# expansion_module_triple_I2C.net
KiCad netlist of a schematic drawn in EAGLE
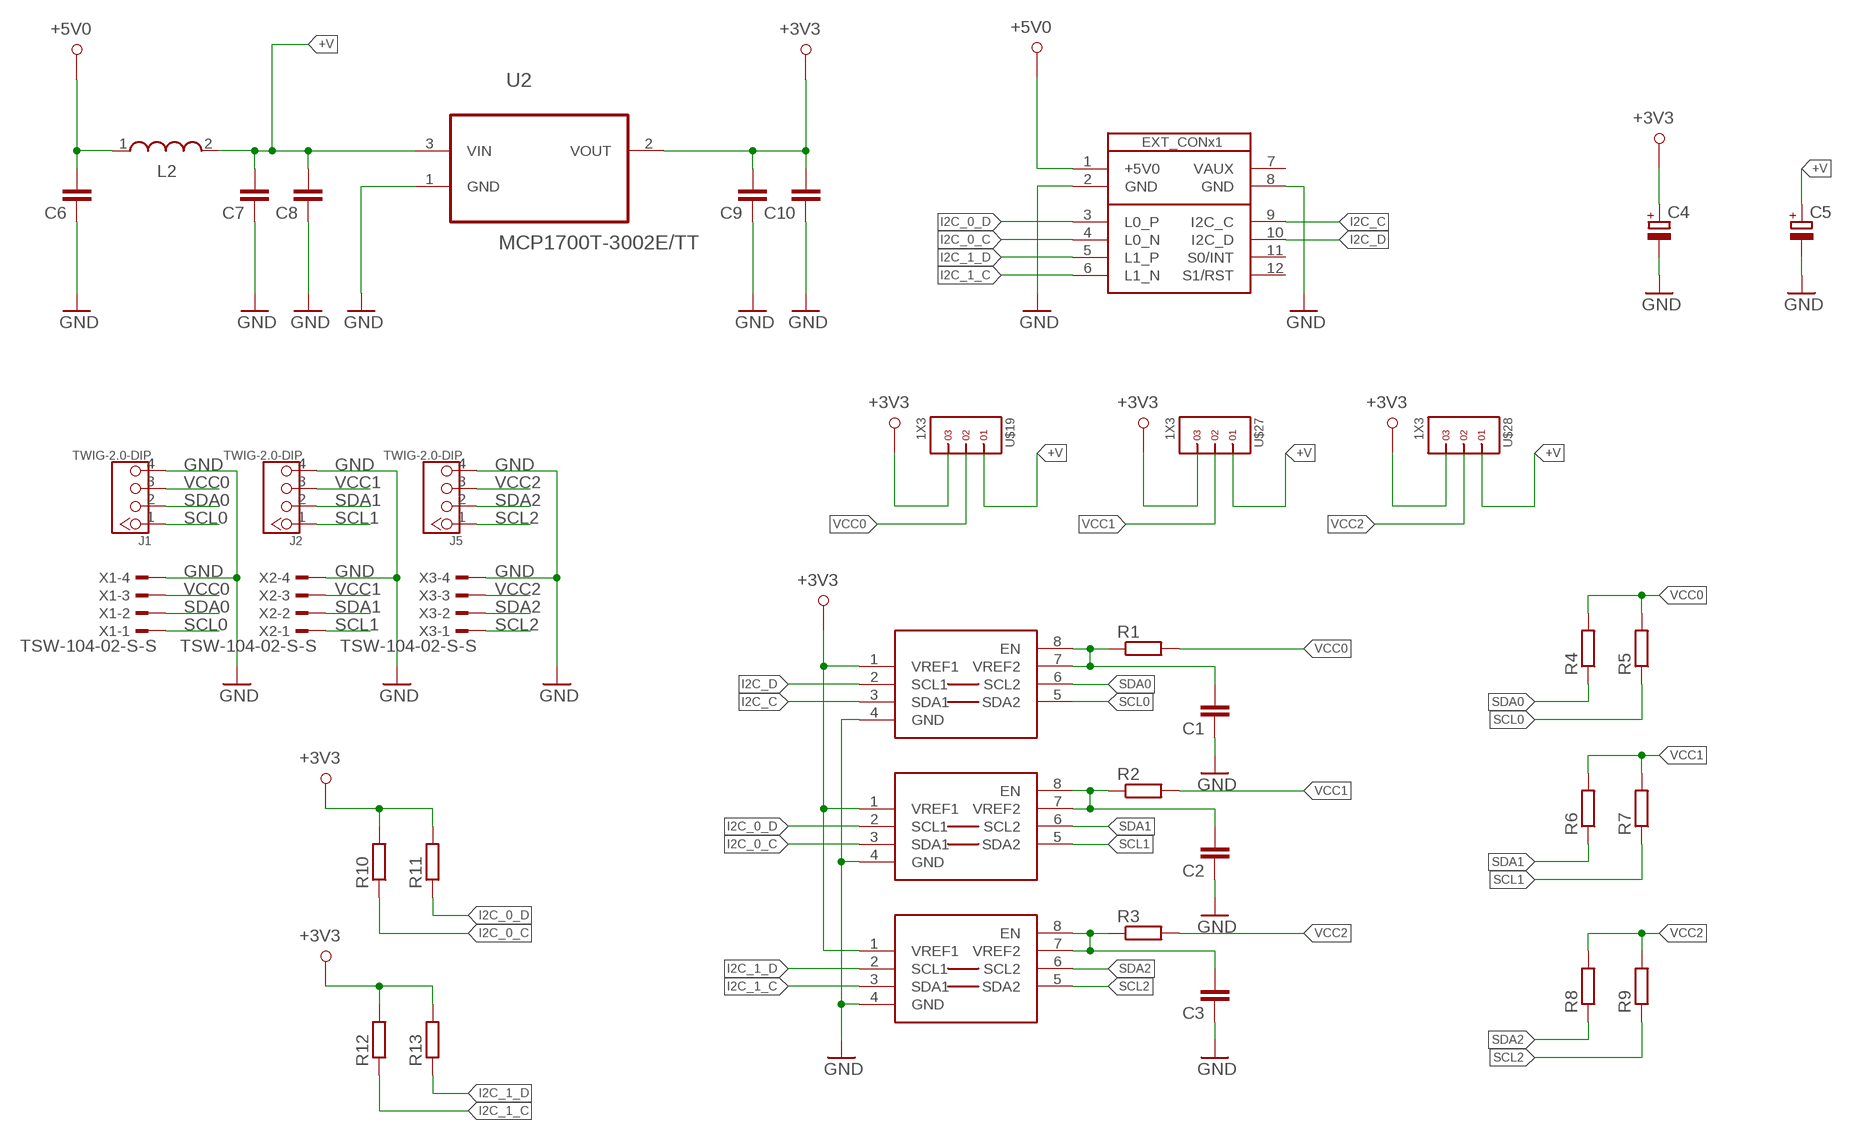
[diagram p0: schematic, sheet 1]

(export (version "E")
  (design (tool "Eeschema 10.0.6"))
  (components
    (comp (ref "C1")
      (value "C-EUC0603")
      (footprint "eagle-import:C0603")
      (libsource (lib "eagle-import") (part "C-EUC0603"))
    )
    (comp (ref "C2")
      (value "C-EUC0603")
      (footprint "eagle-import:C0603")
      (libsource (lib "eagle-import") (part "C-EUC0603"))
    )
    (comp (ref "C3")
      (value "C-EUC0603")
      (footprint "eagle-import:C0603")
      (libsource (lib "eagle-import") (part "C-EUC0603"))
    )
    (comp (ref "C4")
      (value "CPOL-EUSMCB")
      (footprint "eagle-import:SMC_B")
      (libsource (lib "eagle-import") (part "CPOL-EUSMCB"))
    )
    (comp (ref "C5")
      (value "CPOL-EUSMCB")
      (footprint "eagle-import:SMC_B")
      (libsource (lib "eagle-import") (part "CPOL-EUSMCB"))
    )
    (comp (ref "C6")
      (value "C-EUC0603")
      (footprint "eagle-import:C0603")
      (libsource (lib "eagle-import") (part "C-EUC0603"))
    )
    (comp (ref "C7")
      (value "C-EUC0603")
      (footprint "eagle-import:C0603")
      (libsource (lib "eagle-import") (part "C-EUC0603"))
    )
    (comp (ref "C8")
      (value "C-EUC0603")
      (footprint "eagle-import:C0603")
      (libsource (lib "eagle-import") (part "C-EUC0603"))
    )
    (comp (ref "C9")
      (value "C-EUC0603")
      (footprint "eagle-import:C0603")
      (libsource (lib "eagle-import") (part "C-EUC0603"))
    )
    (comp (ref "C10")
      (value "C-EUC0603")
      (footprint "eagle-import:C0603")
      (libsource (lib "eagle-import") (part "C-EUC0603"))
    )
    (comp (ref "J1")
      (value "TWIG-2.0-DIP")
      (footprint "eagle-import:2.0_1X4")
      (libsource (lib "eagle-import") (part "TWIG-2.0-DIP"))
    )
    (comp (ref "J2")
      (value "TWIG-2.0-DIP")
      (footprint "eagle-import:2.0_1X4")
      (libsource (lib "eagle-import") (part "TWIG-2.0-DIP"))
    )
    (comp (ref "J5")
      (value "TWIG-2.0-DIP")
      (footprint "eagle-import:2.0_1X4")
      (libsource (lib "eagle-import") (part "TWIG-2.0-DIP"))
    )
    (comp (ref "L2")
      (value "WE-LQ_1210")
      (footprint "eagle-import:WE-LQ_M")
      (libsource (lib "eagle-import") (part "WE-LQ_1210"))
    )
    (comp (ref "R1")
      (value "R-EU_R0603")
      (footprint "eagle-import:R0603")
      (libsource (lib "eagle-import") (part "R-EU_R0603"))
    )
    (comp (ref "R2")
      (value "R-EU_R0603")
      (footprint "eagle-import:R0603")
      (libsource (lib "eagle-import") (part "R-EU_R0603"))
    )
    (comp (ref "R3")
      (value "R-EU_R0603")
      (footprint "eagle-import:R0603")
      (libsource (lib "eagle-import") (part "R-EU_R0603"))
    )
    (comp (ref "R4")
      (value "R-EU_R0603")
      (footprint "eagle-import:R0603")
      (libsource (lib "eagle-import") (part "R-EU_R0603"))
    )
    (comp (ref "R5")
      (value "R-EU_R0603")
      (footprint "eagle-import:R0603")
      (libsource (lib "eagle-import") (part "R-EU_R0603"))
    )
    (comp (ref "R6")
      (value "R-EU_R0603")
      (footprint "eagle-import:R0603")
      (libsource (lib "eagle-import") (part "R-EU_R0603"))
    )
    (comp (ref "R7")
      (value "R-EU_R0603")
      (footprint "eagle-import:R0603")
      (libsource (lib "eagle-import") (part "R-EU_R0603"))
    )
    (comp (ref "R8")
      (value "R-EU_R0603")
      (footprint "eagle-import:R0603")
      (libsource (lib "eagle-import") (part "R-EU_R0603"))
    )
    (comp (ref "R9")
      (value "R-EU_R0603")
      (footprint "eagle-import:R0603")
      (libsource (lib "eagle-import") (part "R-EU_R0603"))
    )
    (comp (ref "R10")
      (value "R-EU_R0603")
      (footprint "eagle-import:R0603")
      (libsource (lib "eagle-import") (part "R-EU_R0603"))
    )
    (comp (ref "R11")
      (value "R-EU_R0603")
      (footprint "eagle-import:R0603")
      (libsource (lib "eagle-import") (part "R-EU_R0603"))
    )
    (comp (ref "R12")
      (value "R-EU_R0603")
      (footprint "eagle-import:R0603")
      (libsource (lib "eagle-import") (part "R-EU_R0603"))
    )
    (comp (ref "R13")
      (value "R-EU_R0603")
      (footprint "eagle-import:R0603")
      (libsource (lib "eagle-import") (part "R-EU_R0603"))
    )
    (comp (ref "U$2")
      (value "SB_EXT_CON_X1")
      (footprint "eagle-import:SB_EXT_CON_X1_FULL")
      (libsource (lib "eagle-import") (part "SB_EXT_CON_X1"))
    )
    (comp (ref "U$16")
      (value "PCA9306")
      (footprint "eagle-import:PSOP-8")
      (libsource (lib "eagle-import") (part "PCA9306"))
    )
    (comp (ref "U$19")
      (value "1X3")
      (footprint "eagle-import:1X3")
      (libsource (lib "eagle-import") (part "1X3"))
    )
    (comp (ref "U$20")
      (value "PCA9306")
      (footprint "eagle-import:PSOP-8")
      (libsource (lib "eagle-import") (part "PCA9306"))
    )
    (comp (ref "U$27")
      (value "1X3")
      (footprint "eagle-import:1X3")
      (libsource (lib "eagle-import") (part "1X3"))
    )
    (comp (ref "U$28")
      (value "1X3")
      (footprint "eagle-import:1X3")
      (libsource (lib "eagle-import") (part "1X3"))
    )
    (comp (ref "U$31")
      (value "PCA9306")
      (footprint "eagle-import:PSOP-8")
      (libsource (lib "eagle-import") (part "PCA9306"))
    )
    (comp (ref "U2")
      (value "MCP1700T-3002E/TT")
      (footprint "eagle-import:SOT95P237X112-3N")
      (libsource (lib "eagle-import") (part "MCP1700T-3002E/TT"))
    )
    (comp (ref "X1")
      (value "TSW-104-02-S-S")
      (footprint "eagle-import:TSW-104-02-S-S")
      (libsource (lib "eagle-import") (part "TSW-104-02-S-S"))
    )
    (comp (ref "X2")
      (value "TSW-104-02-S-S")
      (footprint "eagle-import:TSW-104-02-S-S")
      (libsource (lib "eagle-import") (part "TSW-104-02-S-S"))
    )
    (comp (ref "X3")
      (value "TSW-104-02-S-S")
      (footprint "eagle-import:TSW-104-02-S-S")
      (libsource (lib "eagle-import") (part "TSW-104-02-S-S"))
    )
  )
  (nets
    (net (code "1") (name "+3V3") (class "Default")
      (node (ref "C10") (pin "2") (pinfunction "2_2") (pintype "passive"))
      (node (ref "C4") (pin "+") (pinfunction "+_+") (pintype "passive"))
      (node (ref "C9") (pin "2") (pinfunction "2_2") (pintype "passive"))
      (node (ref "R10") (pin "2") (pinfunction "2_2") (pintype "passive"))
      (node (ref "R11") (pin "2") (pinfunction "2_2") (pintype "passive"))
      (node (ref "R12") (pin "2") (pinfunction "2_2") (pintype "passive"))
      (node (ref "R13") (pin "2") (pinfunction "2_2") (pintype "passive"))
      (node (ref "U$16") (pin "1") (pinfunction "VREF1_1") (pintype "bidirectional"))
      (node (ref "U$19") (pin "3") (pinfunction "3_3") (pintype "bidirectional"))
      (node (ref "U$20") (pin "1") (pinfunction "VREF1_1") (pintype "bidirectional"))
      (node (ref "U$27") (pin "3") (pinfunction "3_3") (pintype "bidirectional"))
      (node (ref "U$28") (pin "3") (pinfunction "3_3") (pintype "bidirectional"))
      (node (ref "U$31") (pin "1") (pinfunction "VREF1_1") (pintype "bidirectional"))
      (node (ref "U2") (pin "2") (pinfunction "VOUT_2") (pintype "output"))
    )
    (net (code "2") (name "+5V0") (class "Default")
      (node (ref "C6") (pin "2") (pinfunction "2_2") (pintype "passive"))
      (node (ref "L2") (pin "1") (pinfunction "1_1") (pintype "passive"))
      (node (ref "U$2") (pin "1") (pinfunction "+5V0_1") (pintype "bidirectional"))
    )
    (net (code "3") (name "+V") (class "Default")
      (node (ref "C5") (pin "+") (pinfunction "+_+") (pintype "passive"))
      (node (ref "C7") (pin "2") (pinfunction "2_2") (pintype "passive"))
      (node (ref "C8") (pin "2") (pinfunction "2_2") (pintype "passive"))
      (node (ref "L2") (pin "2") (pinfunction "2_2") (pintype "passive"))
      (node (ref "U$19") (pin "1") (pinfunction "1_1") (pintype "bidirectional"))
      (node (ref "U$27") (pin "1") (pinfunction "1_1") (pintype "bidirectional"))
      (node (ref "U$28") (pin "1") (pinfunction "1_1") (pintype "bidirectional"))
      (node (ref "U2") (pin "3") (pinfunction "VIN_3") (pintype "input"))
    )
    (net (code "4") (name "GND") (class "Default")
      (node (ref "C1") (pin "1") (pinfunction "1_1") (pintype "passive"))
      (node (ref "C10") (pin "1") (pinfunction "1_1") (pintype "passive"))
      (node (ref "C2") (pin "1") (pinfunction "1_1") (pintype "passive"))
      (node (ref "C3") (pin "1") (pinfunction "1_1") (pintype "passive"))
      (node (ref "C4") (pin "-") (pinfunction "-_-") (pintype "passive"))
      (node (ref "C5") (pin "-") (pinfunction "-_-") (pintype "passive"))
      (node (ref "C6") (pin "1") (pinfunction "1_1") (pintype "passive"))
      (node (ref "C7") (pin "1") (pinfunction "1_1") (pintype "passive"))
      (node (ref "C8") (pin "1") (pinfunction "1_1") (pintype "passive"))
      (node (ref "C9") (pin "1") (pinfunction "1_1") (pintype "passive"))
      (node (ref "J1") (pin "4") (pinfunction "4_4") (pintype "bidirectional"))
      (node (ref "J2") (pin "4") (pinfunction "4_4") (pintype "bidirectional"))
      (node (ref "J5") (pin "4") (pinfunction "4_4") (pintype "bidirectional"))
      (node (ref "U$16") (pin "4") (pinfunction "GND_4") (pintype "bidirectional"))
      (node (ref "U$2") (pin "2") (pinfunction "GND_2") (pintype "bidirectional"))
      (node (ref "U$2") (pin "8") (pinfunction "GND_8") (pintype "bidirectional"))
      (node (ref "U$20") (pin "4") (pinfunction "GND_4") (pintype "bidirectional"))
      (node (ref "U$31") (pin "4") (pinfunction "GND_4") (pintype "bidirectional"))
      (node (ref "U2") (pin "1") (pinfunction "GND_1") (pintype "passive"))
      (node (ref "X1") (pin "4") (pinfunction "1_4") (pintype "passive"))
      (node (ref "X2") (pin "4") (pinfunction "1_4") (pintype "passive"))
      (node (ref "X3") (pin "4") (pinfunction "1_4") (pintype "passive"))
    )
    (net (code "5") (name "I2C_0_C") (class "Default")
      (node (ref "R10") (pin "1") (pinfunction "1_1") (pintype "passive"))
      (node (ref "U$2") (pin "4") (pinfunction "L0_N_4") (pintype "bidirectional"))
      (node (ref "U$20") (pin "3") (pinfunction "SDA1_3") (pintype "bidirectional"))
    )
    (net (code "6") (name "I2C_0_D") (class "Default")
      (node (ref "R11") (pin "1") (pinfunction "1_1") (pintype "passive"))
      (node (ref "U$2") (pin "3") (pinfunction "L0_P_3") (pintype "bidirectional"))
      (node (ref "U$20") (pin "2") (pinfunction "SCL1_2") (pintype "bidirectional"))
    )
    (net (code "7") (name "I2C_1_C") (class "Default")
      (node (ref "R12") (pin "1") (pinfunction "1_1") (pintype "passive"))
      (node (ref "U$2") (pin "6") (pinfunction "L1_N_6") (pintype "bidirectional"))
      (node (ref "U$31") (pin "3") (pinfunction "SDA1_3") (pintype "bidirectional"))
    )
    (net (code "8") (name "I2C_1_D") (class "Default")
      (node (ref "R13") (pin "1") (pinfunction "1_1") (pintype "passive"))
      (node (ref "U$2") (pin "5") (pinfunction "L1_P_5") (pintype "bidirectional"))
      (node (ref "U$31") (pin "2") (pinfunction "SCL1_2") (pintype "bidirectional"))
    )
    (net (code "9") (name "I2C_C") (class "Default")
      (node (ref "U$16") (pin "3") (pinfunction "SDA1_3") (pintype "bidirectional"))
      (node (ref "U$2") (pin "9") (pinfunction "I2C_C_9") (pintype "bidirectional"))
    )
    (net (code "10") (name "I2C_D") (class "Default")
      (node (ref "U$16") (pin "2") (pinfunction "SCL1_2") (pintype "bidirectional"))
      (node (ref "U$2") (pin "10") (pinfunction "I2C_D_10") (pintype "bidirectional"))
    )
    (net (code "11") (name "Net-(U$16-EN)") (class "Default")
      (node (ref "C1") (pin "2") (pinfunction "2_2") (pintype "passive"))
      (node (ref "R1") (pin "1") (pinfunction "1_1") (pintype "passive"))
      (node (ref "U$16") (pin "7") (pinfunction "VREF2_7") (pintype "bidirectional"))
      (node (ref "U$16") (pin "8") (pinfunction "EN_8") (pintype "bidirectional"))
    )
    (net (code "12") (name "Net-(U$20-EN)") (class "Default")
      (node (ref "C2") (pin "2") (pinfunction "2_2") (pintype "passive"))
      (node (ref "R2") (pin "1") (pinfunction "1_1") (pintype "passive"))
      (node (ref "U$20") (pin "7") (pinfunction "VREF2_7") (pintype "bidirectional"))
      (node (ref "U$20") (pin "8") (pinfunction "EN_8") (pintype "bidirectional"))
    )
    (net (code "13") (name "Net-(U$31-EN)") (class "Default")
      (node (ref "C3") (pin "2") (pinfunction "2_2") (pintype "passive"))
      (node (ref "R3") (pin "1") (pinfunction "1_1") (pintype "passive"))
      (node (ref "U$31") (pin "7") (pinfunction "VREF2_7") (pintype "bidirectional"))
      (node (ref "U$31") (pin "8") (pinfunction "EN_8") (pintype "bidirectional"))
    )
    (net (code "14") (name "SCL0") (class "Default")
      (node (ref "J1") (pin "1") (pinfunction "1_1") (pintype "bidirectional"))
      (node (ref "R5") (pin "1") (pinfunction "1_1") (pintype "passive"))
      (node (ref "U$16") (pin "5") (pinfunction "SDA2_5") (pintype "bidirectional"))
      (node (ref "X1") (pin "1") (pinfunction "1_1") (pintype "passive"))
    )
    (net (code "15") (name "SCL1") (class "Default")
      (node (ref "J2") (pin "1") (pinfunction "1_1") (pintype "bidirectional"))
      (node (ref "R7") (pin "1") (pinfunction "1_1") (pintype "passive"))
      (node (ref "U$20") (pin "5") (pinfunction "SDA2_5") (pintype "bidirectional"))
      (node (ref "X2") (pin "1") (pinfunction "1_1") (pintype "passive"))
    )
    (net (code "16") (name "SCL2") (class "Default")
      (node (ref "J5") (pin "1") (pinfunction "1_1") (pintype "bidirectional"))
      (node (ref "R9") (pin "1") (pinfunction "1_1") (pintype "passive"))
      (node (ref "U$31") (pin "5") (pinfunction "SDA2_5") (pintype "bidirectional"))
      (node (ref "X3") (pin "1") (pinfunction "1_1") (pintype "passive"))
    )
    (net (code "17") (name "SDA0") (class "Default")
      (node (ref "J1") (pin "2") (pinfunction "2_2") (pintype "bidirectional"))
      (node (ref "R4") (pin "1") (pinfunction "1_1") (pintype "passive"))
      (node (ref "U$16") (pin "6") (pinfunction "SCL2_6") (pintype "bidirectional"))
      (node (ref "X1") (pin "2") (pinfunction "1_2") (pintype "passive"))
    )
    (net (code "18") (name "SDA1") (class "Default")
      (node (ref "J2") (pin "2") (pinfunction "2_2") (pintype "bidirectional"))
      (node (ref "R6") (pin "1") (pinfunction "1_1") (pintype "passive"))
      (node (ref "U$20") (pin "6") (pinfunction "SCL2_6") (pintype "bidirectional"))
      (node (ref "X2") (pin "2") (pinfunction "1_2") (pintype "passive"))
    )
    (net (code "19") (name "SDA2") (class "Default")
      (node (ref "J5") (pin "2") (pinfunction "2_2") (pintype "bidirectional"))
      (node (ref "R8") (pin "1") (pinfunction "1_1") (pintype "passive"))
      (node (ref "U$31") (pin "6") (pinfunction "SCL2_6") (pintype "bidirectional"))
      (node (ref "X3") (pin "2") (pinfunction "1_2") (pintype "passive"))
    )
    (net (code "20") (name "VCC0") (class "Default")
      (node (ref "J1") (pin "3") (pinfunction "3_3") (pintype "bidirectional"))
      (node (ref "R1") (pin "2") (pinfunction "2_2") (pintype "passive"))
      (node (ref "R4") (pin "2") (pinfunction "2_2") (pintype "passive"))
      (node (ref "R5") (pin "2") (pinfunction "2_2") (pintype "passive"))
      (node (ref "U$19") (pin "2") (pinfunction "2_2") (pintype "bidirectional"))
      (node (ref "X1") (pin "3") (pinfunction "1_3") (pintype "passive"))
    )
    (net (code "21") (name "VCC1") (class "Default")
      (node (ref "J2") (pin "3") (pinfunction "3_3") (pintype "bidirectional"))
      (node (ref "R2") (pin "2") (pinfunction "2_2") (pintype "passive"))
      (node (ref "R6") (pin "2") (pinfunction "2_2") (pintype "passive"))
      (node (ref "R7") (pin "2") (pinfunction "2_2") (pintype "passive"))
      (node (ref "U$27") (pin "2") (pinfunction "2_2") (pintype "bidirectional"))
      (node (ref "X2") (pin "3") (pinfunction "1_3") (pintype "passive"))
    )
    (net (code "22") (name "VCC2") (class "Default")
      (node (ref "J5") (pin "3") (pinfunction "3_3") (pintype "bidirectional"))
      (node (ref "R3") (pin "2") (pinfunction "2_2") (pintype "passive"))
      (node (ref "R8") (pin "2") (pinfunction "2_2") (pintype "passive"))
      (node (ref "R9") (pin "2") (pinfunction "2_2") (pintype "passive"))
      (node (ref "U$28") (pin "2") (pinfunction "2_2") (pintype "bidirectional"))
      (node (ref "X3") (pin "3") (pinfunction "1_3") (pintype "passive"))
    )
    (net (code "23") (name "unconnected-(U$2-S0{slash}INT-Pad11)") (class "Default")
      (node (ref "U$2") (pin "11") (pinfunction "S0/INT_11") (pintype "bidirectional"))
    )
    (net (code "24") (name "unconnected-(U$2-S1{slash}RST-Pad12)") (class "Default")
      (node (ref "U$2") (pin "12") (pinfunction "S1/RST_12") (pintype "bidirectional"))
    )
    (net (code "25") (name "unconnected-(U$2-VAUX-Pad7)") (class "Default")
      (node (ref "U$2") (pin "7") (pinfunction "VAUX_7") (pintype "bidirectional"))
    )
  )
)
